# phantom_power.net
KiCad netlist of a schematic drawn in EAGLE
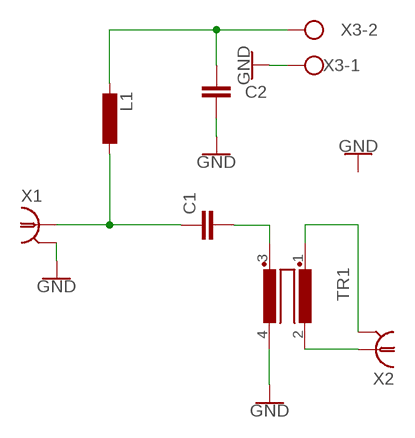
[diagram p0: schematic, sheet 1]

(export (version "E")
  (design (tool "Eeschema 10.0.6"))
  (components
    (comp (ref "C1")
      (value "C-EUC1206K")
      (footprint "eagle-import:C1206K")
      (libsource (lib "eagle-import") (part "C-EUC1206K"))
    )
    (comp (ref "C2")
      (value "C-EUC1206K")
      (footprint "eagle-import:C1206K")
      (libsource (lib "eagle-import") (part "C-EUC1206K"))
    )
    (comp (ref "L1")
      (value "L-EU6000-XXX-RC")
      (footprint "eagle-import:6000-XXXX-RC")
      (libsource (lib "eagle-import") (part "L-EU6000-XXX-RC"))
    )
    (comp (ref "TR1")
      (value "R1405UB1/2")
      (footprint "eagle-import:B1_2")
      (libsource (lib "eagle-import") (part "R1405UB1/2"))
    )
    (comp (ref "X1")
      (value "227161-8")
      (footprint "eagle-import:AMP_227161")
      (libsource (lib "eagle-import") (part "?227161-8"))
    )
    (comp (ref "X2")
      (value "227161-8")
      (footprint "eagle-import:AMP_227161")
      (libsource (lib "eagle-import") (part "?227161-8"))
    )
    (comp (ref "X3")
      (value "W237-102")
      (footprint "eagle-import:W237-102")
      (fields (field (name "MPN") "237-102"))
      (libsource (lib "eagle-import") (part "W237-102"))
    )
  )
  (nets
    (net (code "1") (name "GND") (class "Default")
      (node (ref "C2") (pin "2") (pinfunction "2_2") (pintype "passive"))
      (node (ref "TR1") (pin "4") (pinfunction "4_4") (pintype "passive"))
      (node (ref "X1") (pin "2") (pinfunction "2_2") (pintype "passive"))
      (node (ref "X3") (pin "1") (pinfunction "KL_1") (pintype "passive"))
    )
    (net (code "2") (name "Net-(C1-Pad1)") (class "Default")
      (node (ref "C1") (pin "1") (pinfunction "1_1") (pintype "passive"))
      (node (ref "L1") (pin "1") (pinfunction "1_1") (pintype "passive"))
      (node (ref "X1") (pin "1") (pinfunction "1_1") (pintype "passive"))
    )
    (net (code "3") (name "Net-(C1-Pad2)") (class "Default")
      (node (ref "C1") (pin "2") (pinfunction "2_2") (pintype "passive"))
      (node (ref "TR1") (pin "3") (pinfunction "3_3") (pintype "passive"))
    )
    (net (code "4") (name "Net-(TR1-Pad1)") (class "Default")
      (node (ref "TR1") (pin "1") (pinfunction "1_1") (pintype "passive"))
      (node (ref "X2") (pin "2") (pinfunction "2_2") (pintype "passive"))
    )
    (net (code "5") (name "Net-(TR1-Pad2)") (class "Default")
      (node (ref "TR1") (pin "2") (pinfunction "2_2") (pintype "passive"))
      (node (ref "X2") (pin "1") (pinfunction "1_1") (pintype "passive"))
    )
    (net (code "6") (name "Net-(X3B-KL)") (class "Default")
      (node (ref "C2") (pin "1") (pinfunction "1_1") (pintype "passive"))
      (node (ref "L1") (pin "2") (pinfunction "2_2") (pintype "passive"))
      (node (ref "X3") (pin "2") (pinfunction "KL_2") (pintype "passive"))
    )
  )
)
